# temp.net
KiCad netlist of a schematic drawn in Altium Designer
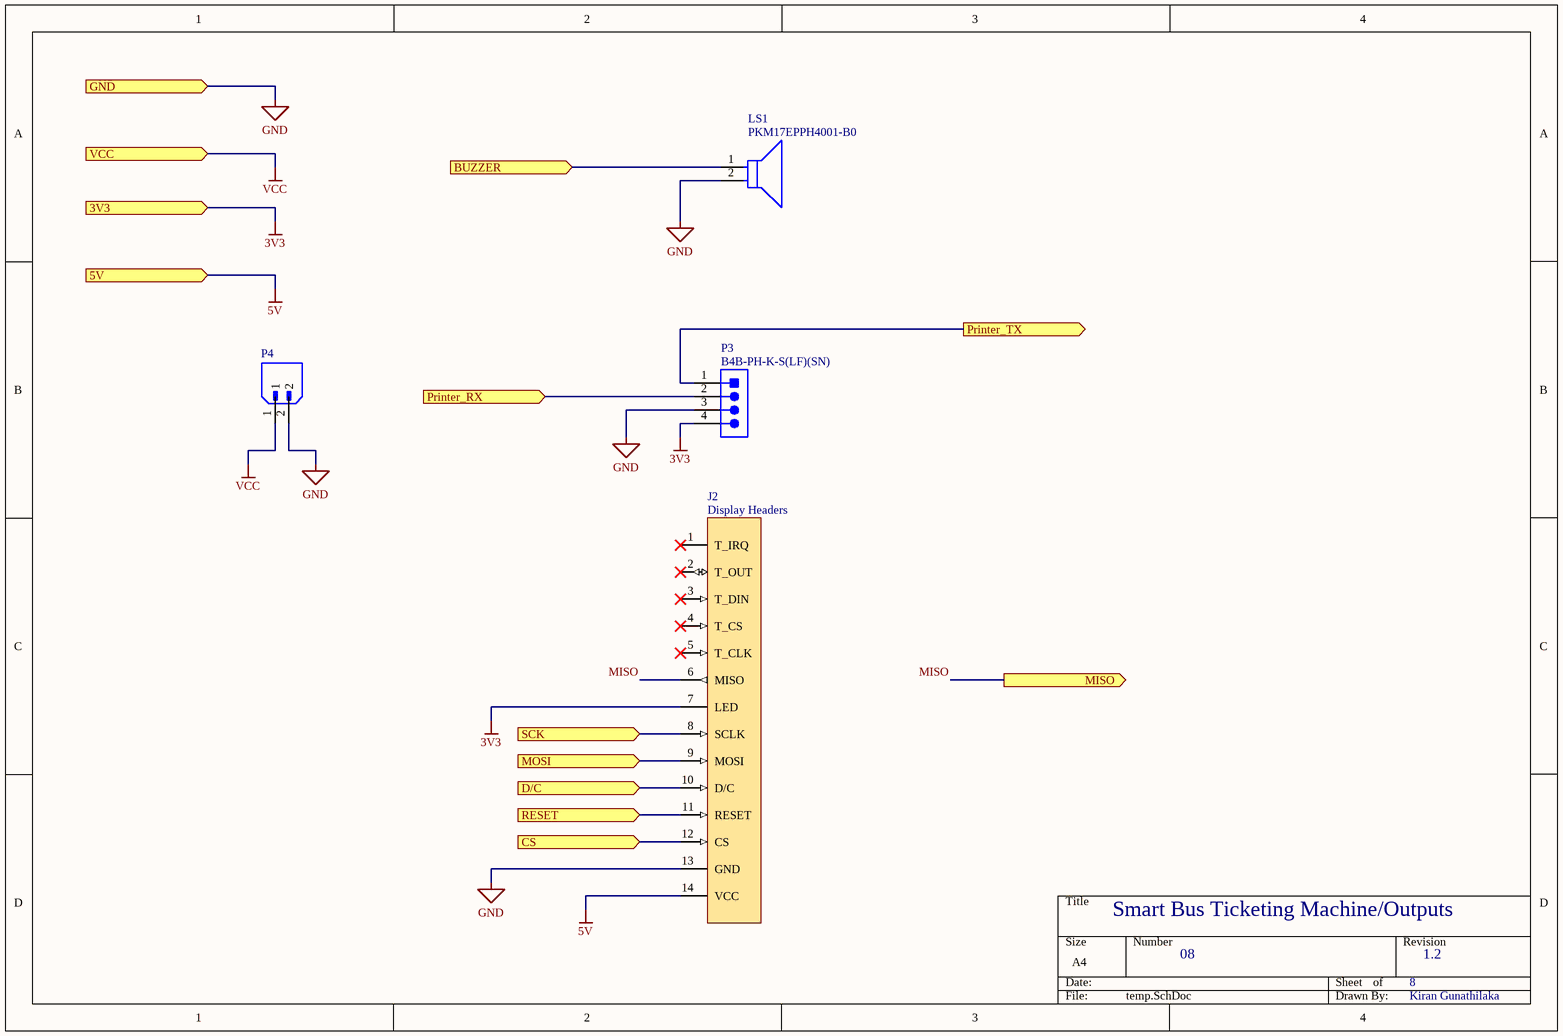
[diagram p0: temp.SchDoc]

(export (version "E")
  (design (tool "Eeschema 10.0.6"))
  (components
    (comp (ref "J2")
      (value "Display Headers")
      (footprint "SULLINS_PPTC061LFBN-RC")
      (libsource (lib "Schlib1") (part "TFT-LCD-2.8'' Display Headers"))
    )
    (comp (ref "LS1")
      (value "PKM17EPPH4001-B0")
      (footprint "FP-PKM17EPPH4001-B0-MFG")
      (description "AUDIO PIEZO TRANSDUCER 25V TH")
      (libsource (lib "Altium Content Vault") (part "5f581d31613f872430949aa526fd155"))
    )
    (comp (ref "P3")
      (value "B4B-PH-K-S(LF)(SN)")
      (footprint "JST-B4B-PH-K-S_V")
      (fields (field (name "MANUFACTURER") "JST"))
      (libsource (lib "Altium Content Vault") (part "CN-1P-M-R4"))
    )
    (comp (ref "P4")
      (value "Battery Connector")
      (footprint "JST_B2B-XH-A(LF)(SN)")
      (libsource (lib "SchemLib") (part "TX_RX Header"))
    )
  )
  (nets
    (net (code "1") (name "/BUZZER") (class "Default")
      (node (ref "LS1") (pin "1") (pinfunction "1_1") (pintype "passive"))
    )
    (net (code "2") (name "/CS") (class "Default")
      (node (ref "J2") (pin "12") (pinfunction "CS_12") (pintype "input"))
    )
    (net (code "3") (name "/D{slash}C") (class "Default")
      (node (ref "J2") (pin "10") (pinfunction "D/C_10") (pintype "input"))
    )
    (net (code "4") (name "/MISO") (class "Default")
      (node (ref "J2") (pin "6") (pinfunction "MISO_6") (pintype "output"))
    )
    (net (code "5") (name "/MOSI") (class "Default")
      (node (ref "J2") (pin "9") (pinfunction "MOSI_9") (pintype "input"))
    )
    (net (code "6") (name "/Printer_RX") (class "Default")
      (node (ref "P3") (pin "2") (pinfunction "2_2") (pintype "passive"))
    )
    (net (code "7") (name "/Printer_TX") (class "Default")
      (node (ref "P3") (pin "1") (pinfunction "1_1") (pintype "passive"))
    )
    (net (code "8") (name "/RESET") (class "Default")
      (node (ref "J2") (pin "11") (pinfunction "RESET_11") (pintype "input"))
    )
    (net (code "9") (name "/SCK") (class "Default")
      (node (ref "J2") (pin "8") (pinfunction "SCLK_8") (pintype "input"))
    )
    (net (code "10") (name "3V3") (class "Default")
      (node (ref "J2") (pin "7") (pinfunction "LED_7") (pintype "passive"))
      (node (ref "P3") (pin "4") (pinfunction "4_4") (pintype "passive"))
    )
    (net (code "11") (name "5V") (class "Default")
      (node (ref "J2") (pin "14") (pinfunction "VCC_14") (pintype "passive"))
    )
    (net (code "12") (name "GND") (class "Default")
      (node (ref "J2") (pin "13") (pinfunction "GND_13") (pintype "passive"))
      (node (ref "LS1") (pin "2") (pinfunction "2_2") (pintype "passive"))
      (node (ref "P3") (pin "3") (pinfunction "3_3") (pintype "passive"))
      (node (ref "P4") (pin "2") (pinfunction "2_2") (pintype "passive"))
    )
    (net (code "13") (name "VCC") (class "Default")
      (node (ref "P4") (pin "1") (pinfunction "1_1") (pintype "passive"))
    )
    (net (code "14") (name "unconnected-(J2-T_CLK-Pad5)") (class "Default")
      (node (ref "J2") (pin "5") (pinfunction "T_CLK_5") (pintype "input+no_connect"))
    )
    (net (code "15") (name "unconnected-(J2-T_CS-Pad4)") (class "Default")
      (node (ref "J2") (pin "4") (pinfunction "T_CS_4") (pintype "input+no_connect"))
    )
    (net (code "16") (name "unconnected-(J2-T_DIN-Pad3)") (class "Default")
      (node (ref "J2") (pin "3") (pinfunction "T_DIN_3") (pintype "input+no_connect"))
    )
    (net (code "17") (name "unconnected-(J2-T_IRQ-Pad1)") (class "Default")
      (node (ref "J2") (pin "1") (pinfunction "T_IRQ_1") (pintype "passive+no_connect"))
    )
    (net (code "18") (name "unconnected-(J2-T_OUT-Pad2)") (class "Default")
      (node (ref "J2") (pin "2") (pinfunction "T_OUT_2") (pintype "bidirectional+no_connect"))
    )
  )
)
